# DashDAP.net
KiCad netlist of a schematic drawn in Altium Designer
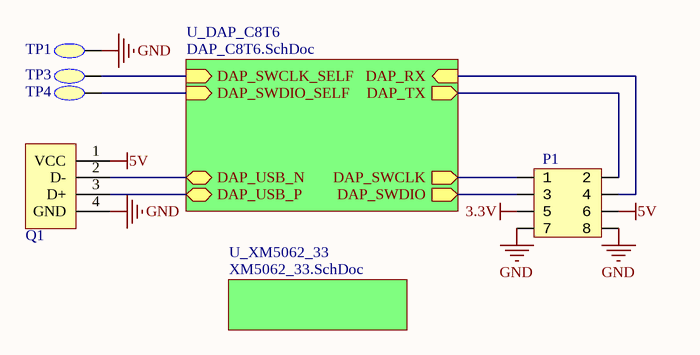
[diagram p0: DashDAP.SchDoc]

(export (version "E")
  (design (tool "Eeschema 10.0.6"))
  (components
    (comp (ref "P1")
      (value "HDR2x4_2.54")
      (footprint "HDR2X4_2.54_180H")
      (description "Header")
      (libsource (lib "Power_Lib_Altium") (part "HDR2x4_2.54"))
    )
    (comp (ref "Q1")
      (value "USB A")
      (footprint "USB-A-male")
      (description "USB 接口")
      (libsource (lib "Power_Lib_Altium") (part "USB A"))
    )
    (comp (ref "TP1")
      (value "TestPoint")
      (footprint "TestPoint")
      (description "测试点")
      (libsource (lib "Power_Lib_Altium") (part "TestPoint"))
    )
    (comp (ref "TP3")
      (value "TestPoint")
      (footprint "TestPoint")
      (description "测试点")
      (libsource (lib "Power_Lib_Altium") (part "TestPoint"))
    )
    (comp (ref "TP4")
      (value "TestPoint")
      (footprint "TestPoint")
      (description "测试点")
      (libsource (lib "Power_Lib_Altium") (part "TestPoint"))
    )
  )
  (nets
    (net (code "1") (name "/DAP_RX") (class "Default")
      (node (ref "P1") (pin "4") (pinfunction "4_4") (pintype "passive"))
    )
    (net (code "2") (name "/DAP_SWCLK") (class "Default")
      (node (ref "P1") (pin "1") (pinfunction "1_1") (pintype "passive"))
    )
    (net (code "3") (name "/DAP_SWCLK_SELF") (class "Default")
      (node (ref "TP3") (pin "1") (pinfunction "1_1") (pintype "passive"))
    )
    (net (code "4") (name "/DAP_SWDIO") (class "Default")
      (node (ref "P1") (pin "3") (pinfunction "3_3") (pintype "passive"))
    )
    (net (code "5") (name "/DAP_SWDIO_SELF") (class "Default")
      (node (ref "TP4") (pin "1") (pinfunction "1_1") (pintype "passive"))
    )
    (net (code "6") (name "/DAP_TX") (class "Default")
      (node (ref "P1") (pin "2") (pinfunction "2_2") (pintype "passive"))
    )
    (net (code "7") (name "/DAP_USB_N") (class "Default")
      (node (ref "Q1") (pin "2") (pinfunction "D-_2") (pintype "passive"))
    )
    (net (code "8") (name "/DAP_USB_P") (class "Default")
      (node (ref "Q1") (pin "3") (pinfunction "D+_3") (pintype "passive"))
    )
    (net (code "9") (name "3.3V") (class "Default")
      (node (ref "P1") (pin "5") (pinfunction "5_5") (pintype "passive"))
    )
    (net (code "10") (name "5V") (class "Default")
      (node (ref "P1") (pin "6") (pinfunction "6_6") (pintype "passive"))
      (node (ref "Q1") (pin "1") (pinfunction "VCC_1") (pintype "passive"))
    )
    (net (code "11") (name "GND") (class "Default")
      (node (ref "P1") (pin "7") (pinfunction "7_7") (pintype "passive"))
      (node (ref "P1") (pin "8") (pinfunction "8_8") (pintype "passive"))
      (node (ref "Q1") (pin "4") (pinfunction "GND_4") (pintype "passive"))
      (node (ref "TP1") (pin "1") (pinfunction "1_1") (pintype "passive"))
    )
  )
)
